# sch.net
KiCad netlist of a schematic drawn in EAGLE
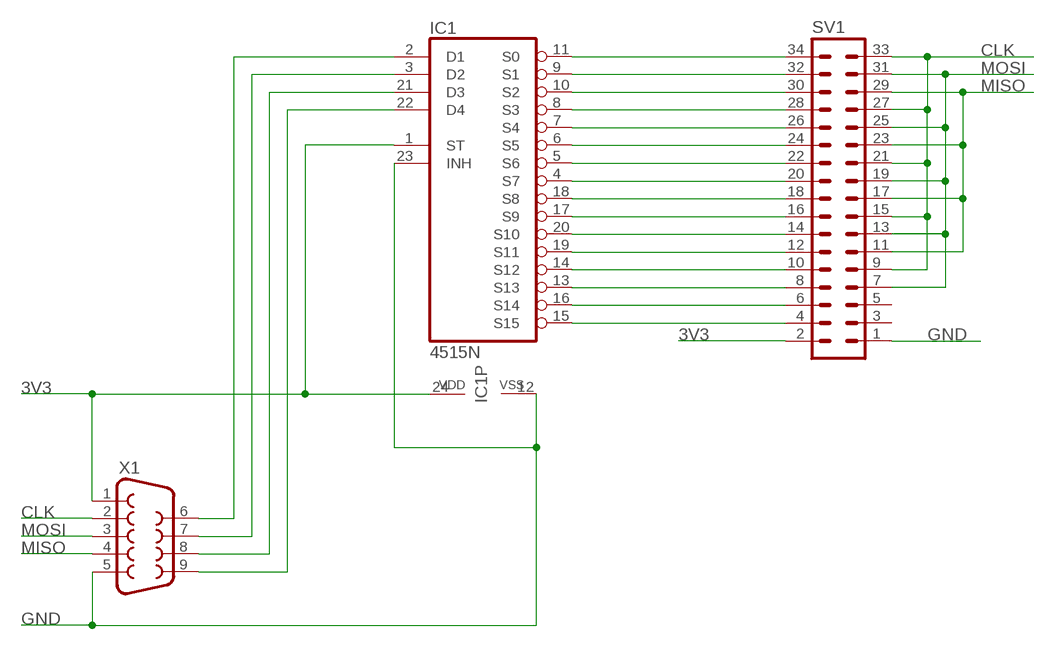
[diagram p0: schematic, sheet 1]

(export (version "E")
  (design (tool "Eeschema 10.0.6"))
  (components
    (comp (ref "IC1")
      (value "4515N")
      (footprint "eagle-import:DIL24-6")
      (libsource (lib "eagle-import") (part "4515N"))
    )
    (comp (ref "SV1")
      (value "MA17-2")
      (footprint "eagle-import:MA17-2")
      (libsource (lib "eagle-import") (part "MA17-2"))
    )
    (comp (ref "X1")
      (value "F09VB")
      (footprint "eagle-import:F09VB")
      (libsource (lib "eagle-import") (part "F09VB"))
    )
  )
  (nets
    (net (code "1") (name "/3V3") (class "Default")
      (node (ref "IC1") (pin "1") (pinfunction "ST_1") (pintype "input"))
      (node (ref "IC1") (pin "24") (pinfunction "VDD_24") (pintype "power_in"))
      (node (ref "SV1") (pin "2") (pinfunction "2_2") (pintype "passive"))
      (node (ref "X1") (pin "1") (pinfunction "1_1") (pintype "passive"))
    )
    (net (code "2") (name "/CLK") (class "Default")
      (node (ref "SV1") (pin "15") (pinfunction "15_15") (pintype "passive"))
      (node (ref "SV1") (pin "21") (pinfunction "21_21") (pintype "passive"))
      (node (ref "SV1") (pin "27") (pinfunction "27_27") (pintype "passive"))
      (node (ref "SV1") (pin "33") (pinfunction "33_33") (pintype "passive"))
      (node (ref "SV1") (pin "9") (pinfunction "9_9") (pintype "passive"))
      (node (ref "X1") (pin "2") (pinfunction "2_2") (pintype "passive"))
    )
    (net (code "3") (name "/GND") (class "Default")
      (node (ref "IC1") (pin "12") (pinfunction "VSS_12") (pintype "power_in"))
      (node (ref "IC1") (pin "23") (pinfunction "INH_23") (pintype "input"))
      (node (ref "SV1") (pin "1") (pinfunction "1_1") (pintype "passive"))
      (node (ref "X1") (pin "5") (pinfunction "5_5") (pintype "passive"))
    )
    (net (code "4") (name "/MISO") (class "Default")
      (node (ref "SV1") (pin "11") (pinfunction "11_11") (pintype "passive"))
      (node (ref "SV1") (pin "17") (pinfunction "17_17") (pintype "passive"))
      (node (ref "SV1") (pin "23") (pinfunction "23_23") (pintype "passive"))
      (node (ref "SV1") (pin "29") (pinfunction "29_29") (pintype "passive"))
      (node (ref "X1") (pin "4") (pinfunction "4_4") (pintype "passive"))
    )
    (net (code "5") (name "/MOSI") (class "Default")
      (node (ref "SV1") (pin "13") (pinfunction "13_13") (pintype "passive"))
      (node (ref "SV1") (pin "19") (pinfunction "19_19") (pintype "passive"))
      (node (ref "SV1") (pin "25") (pinfunction "25_25") (pintype "passive"))
      (node (ref "SV1") (pin "31") (pinfunction "31_31") (pintype "passive"))
      (node (ref "SV1") (pin "7") (pinfunction "7_7") (pintype "passive"))
      (node (ref "X1") (pin "3") (pinfunction "3_3") (pintype "passive"))
    )
    (net (code "6") (name "Net-(IC1A-D1)") (class "Default")
      (node (ref "IC1") (pin "2") (pinfunction "D1_2") (pintype "input"))
      (node (ref "X1") (pin "6") (pinfunction "6_6") (pintype "passive"))
    )
    (net (code "7") (name "Net-(IC1A-D2)") (class "Default")
      (node (ref "IC1") (pin "3") (pinfunction "D2_3") (pintype "input"))
      (node (ref "X1") (pin "7") (pinfunction "7_7") (pintype "passive"))
    )
    (net (code "8") (name "Net-(IC1A-D3)") (class "Default")
      (node (ref "IC1") (pin "21") (pinfunction "D3_21") (pintype "input"))
      (node (ref "X1") (pin "8") (pinfunction "8_8") (pintype "passive"))
    )
    (net (code "9") (name "Net-(IC1A-D4)") (class "Default")
      (node (ref "IC1") (pin "22") (pinfunction "D4_22") (pintype "input"))
      (node (ref "X1") (pin "9") (pinfunction "9_9") (pintype "passive"))
    )
    (net (code "10") (name "Net-(IC1A-S0)") (class "Default")
      (node (ref "IC1") (pin "11") (pinfunction "S0_11") (pintype "output"))
      (node (ref "SV1") (pin "34") (pinfunction "34_34") (pintype "passive"))
    )
    (net (code "11") (name "Net-(IC1A-S1)") (class "Default")
      (node (ref "IC1") (pin "9") (pinfunction "S1_9") (pintype "output"))
      (node (ref "SV1") (pin "32") (pinfunction "32_32") (pintype "passive"))
    )
    (net (code "12") (name "Net-(IC1A-S2)") (class "Default")
      (node (ref "IC1") (pin "10") (pinfunction "S2_10") (pintype "output"))
      (node (ref "SV1") (pin "30") (pinfunction "30_30") (pintype "passive"))
    )
    (net (code "13") (name "Net-(IC1A-S3)") (class "Default")
      (node (ref "IC1") (pin "8") (pinfunction "S3_8") (pintype "output"))
      (node (ref "SV1") (pin "28") (pinfunction "28_28") (pintype "passive"))
    )
    (net (code "14") (name "Net-(IC1A-S4)") (class "Default")
      (node (ref "IC1") (pin "7") (pinfunction "S4_7") (pintype "output"))
      (node (ref "SV1") (pin "26") (pinfunction "26_26") (pintype "passive"))
    )
    (net (code "15") (name "Net-(IC1A-S5)") (class "Default")
      (node (ref "IC1") (pin "6") (pinfunction "S5_6") (pintype "output"))
      (node (ref "SV1") (pin "24") (pinfunction "24_24") (pintype "passive"))
    )
    (net (code "16") (name "Net-(IC1A-S6)") (class "Default")
      (node (ref "IC1") (pin "5") (pinfunction "S6_5") (pintype "output"))
      (node (ref "SV1") (pin "22") (pinfunction "22_22") (pintype "passive"))
    )
    (net (code "17") (name "Net-(IC1A-S7)") (class "Default")
      (node (ref "IC1") (pin "4") (pinfunction "S7_4") (pintype "output"))
      (node (ref "SV1") (pin "20") (pinfunction "20_20") (pintype "passive"))
    )
    (net (code "18") (name "Net-(IC1A-S8)") (class "Default")
      (node (ref "IC1") (pin "18") (pinfunction "S8_18") (pintype "output"))
      (node (ref "SV1") (pin "18") (pinfunction "18_18") (pintype "passive"))
    )
    (net (code "19") (name "Net-(IC1A-S9)") (class "Default")
      (node (ref "IC1") (pin "17") (pinfunction "S9_17") (pintype "output"))
      (node (ref "SV1") (pin "16") (pinfunction "16_16") (pintype "passive"))
    )
    (net (code "20") (name "Net-(IC1A-S10)") (class "Default")
      (node (ref "IC1") (pin "20") (pinfunction "S10_20") (pintype "output"))
      (node (ref "SV1") (pin "14") (pinfunction "14_14") (pintype "passive"))
    )
    (net (code "21") (name "Net-(IC1A-S11)") (class "Default")
      (node (ref "IC1") (pin "19") (pinfunction "S11_19") (pintype "output"))
      (node (ref "SV1") (pin "12") (pinfunction "12_12") (pintype "passive"))
    )
    (net (code "22") (name "Net-(IC1A-S12)") (class "Default")
      (node (ref "IC1") (pin "14") (pinfunction "S12_14") (pintype "output"))
      (node (ref "SV1") (pin "10") (pinfunction "10_10") (pintype "passive"))
    )
    (net (code "23") (name "Net-(IC1A-S13)") (class "Default")
      (node (ref "IC1") (pin "13") (pinfunction "S13_13") (pintype "output"))
      (node (ref "SV1") (pin "8") (pinfunction "8_8") (pintype "passive"))
    )
    (net (code "24") (name "Net-(IC1A-S14)") (class "Default")
      (node (ref "IC1") (pin "16") (pinfunction "S14_16") (pintype "output"))
      (node (ref "SV1") (pin "6") (pinfunction "6_6") (pintype "passive"))
    )
    (net (code "25") (name "Net-(IC1A-S15)") (class "Default")
      (node (ref "IC1") (pin "15") (pinfunction "S15_15") (pintype "output"))
      (node (ref "SV1") (pin "4") (pinfunction "4_4") (pintype "passive"))
    )
    (net (code "26") (name "unconnected-(SV1-Pad3)") (class "Default")
      (node (ref "SV1") (pin "3") (pinfunction "3_3") (pintype "passive"))
    )
    (net (code "27") (name "unconnected-(SV1-Pad5)") (class "Default")
      (node (ref "SV1") (pin "5") (pinfunction "5_5") (pintype "passive"))
    )
  )
)
